# Jetson_Nano_Power_-2.net
KiCad netlist of a schematic drawn in Altium Designer
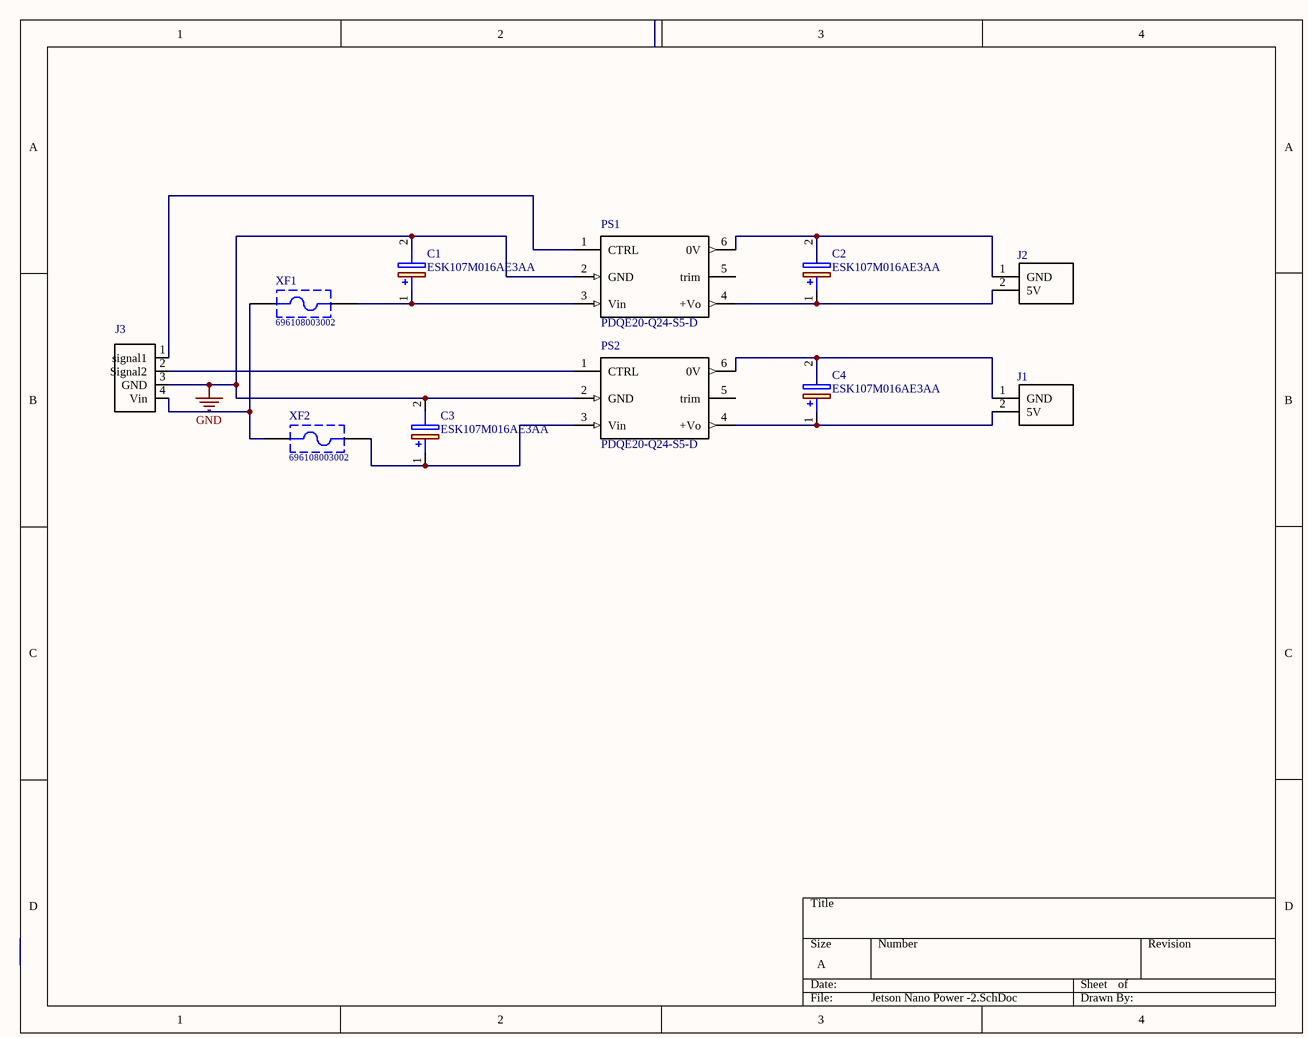
[diagram p0: Jetson Nano Power -2.SchDoc]

(export (version "E")
  (design (tool "Eeschema 10.0.6"))
  (components
    (comp (ref "C1")
      (value "ESK107M016AE3AA")
      (footprint "CAPPRD250W50D630H1250")
      (description "Capacitor Polarised")
      (libsource (lib "80-ESK107M016AE3AA") (part "ESK107M016AE3AA"))
    )
    (comp (ref "C2")
      (value "ESK107M016AE3AA")
      (footprint "CAPPRD250W50D630H1250")
      (description "Capacitor Polarised")
      (libsource (lib "80-ESK107M016AE3AA") (part "ESK107M016AE3AA"))
    )
    (comp (ref "C3")
      (value "ESK107M016AE3AA")
      (footprint "CAPPRD250W50D630H1250")
      (description "Capacitor Polarised")
      (libsource (lib "80-ESK107M016AE3AA") (part "ESK107M016AE3AA"))
    )
    (comp (ref "C4")
      (value "ESK107M016AE3AA")
      (footprint "CAPPRD250W50D630H1250")
      (description "Capacitor Polarised")
      (libsource (lib "80-ESK107M016AE3AA") (part "ESK107M016AE3AA"))
    )
    (comp (ref "J1")
      (value "282856-2")
      (footprint "*TE_282856-2")
      (description "TERMI-BLOK PCB MOUNT 2P")
      (fields (field (name "MF") "TE Connectivity"))
      (libsource (lib "282856-2") (part "282856-2"))
    )
    (comp (ref "J2")
      (value "282856-2")
      (footprint "*TE_282856-2")
      (description "TERMI-BLOK PCB MOUNT 2P")
      (fields (field (name "MF") "TE Connectivity"))
      (libsource (lib "282856-2") (part "282856-2"))
    )
    (comp (ref "J3")
      (value "282836-4")
      (footprint "*TE_282836-4")
      (description "4 Position Wire to Board Terminal Block Horizontal with Board 0.197 _5.00mm_ Through Hole")
      (fields (field (name "MF") "TE Connectivity"))
      (libsource (lib "282836-4") (part "282836-4"))
    )
    (comp (ref "PS1")
      (value "PDQE20-Q24-S5-D")
      (footprint "*CONV_PDQE20-Q24-S5-D")
      (description "20 W, 4:1 Input Range, Single/Dual Regulated Output, DIP, 1500 Vdc Isolation, Dc-Dc Converter")
      (fields (field (name "MF") "CUI Inc.") (field (name "DIGI-KEY_PART_NUMBER") "102-6267-ND"))
      (libsource (lib "PDQE20-Q24-S5-D") (part "PDQE20-Q24-S5-D"))
    )
    (comp (ref "PS2")
      (value "PDQE20-Q24-S5-D")
      (footprint "*CONV_PDQE20-Q24-S5-D")
      (description "20 W, 4:1 Input Range, Single/Dual Regulated Output, DIP, 1500 Vdc Isolation, Dc-Dc Converter")
      (fields (field (name "MF") "CUI Inc.") (field (name "DIGI-KEY_PART_NUMBER") "102-6267-ND"))
      (libsource (lib "PDQE20-Q24-S5-D") (part "PDQE20-Q24-S5-D"))
    )
    (comp (ref "XF1")
      (value "696108003002")
      (footprint "696108003002")
      (description "WR-FSH Fuse Holder Blocks Fuse Holder Blocks Clip Cover for PCB")
      (fields (field (name "MANUFACTURER") "Wurth Elektronik") (field (name "PUBLISHER") "WurthElektronik"))
      (libsource (lib "Altium Content Vault") (part "WE-FUSE-2"))
    )
    (comp (ref "XF2")
      (value "696108003002")
      (footprint "696108003002")
      (description "WR-FSH Fuse Holder Blocks Fuse Holder Blocks Clip Cover for PCB")
      (fields (field (name "MANUFACTURER") "Wurth Elektronik") (field (name "PUBLISHER") "WurthElektronik"))
      (libsource (lib "Altium Content Vault") (part "WE-FUSE-2"))
    )
  )
  (nets
    (net (code "1") (name "GND") (class "Default")
      (node (ref "C1") (pin "2") (pinfunction "-_2") (pintype "passive"))
      (node (ref "C3") (pin "2") (pinfunction "-_2") (pintype "passive"))
      (node (ref "J3") (pin "3") (pinfunction "GND_3") (pintype "passive"))
      (node (ref "PS1") (pin "2") (pinfunction "GND_2") (pintype "input"))
      (node (ref "PS2") (pin "2") (pinfunction "GND_2") (pintype "input"))
    )
    (net (code "2") (name "Net-(C1-+)") (class "Default")
      (node (ref "C1") (pin "1") (pinfunction "+_1") (pintype "passive"))
      (node (ref "PS1") (pin "3") (pinfunction "Vin_3") (pintype "input"))
      (node (ref "XF1") (pin "2") (pinfunction "2_2") (pintype "passive"))
    )
    (net (code "3") (name "Net-(C2-+)") (class "Default")
      (node (ref "C2") (pin "1") (pinfunction "+_1") (pintype "passive"))
      (node (ref "J2") (pin "2") (pinfunction "5V_2") (pintype "passive"))
      (node (ref "PS1") (pin "4") (pinfunction "+Vo_4") (pintype "output"))
    )
    (net (code "4") (name "Net-(C2--)") (class "Default")
      (node (ref "C2") (pin "2") (pinfunction "-_2") (pintype "passive"))
      (node (ref "J2") (pin "1") (pinfunction "GND_1") (pintype "passive"))
      (node (ref "PS1") (pin "6") (pinfunction "0V_6") (pintype "output"))
    )
    (net (code "5") (name "Net-(C3-+)") (class "Default")
      (node (ref "C3") (pin "1") (pinfunction "+_1") (pintype "passive"))
      (node (ref "PS2") (pin "3") (pinfunction "Vin_3") (pintype "input"))
      (node (ref "XF2") (pin "2") (pinfunction "2_2") (pintype "passive"))
    )
    (net (code "6") (name "Net-(C4-+)") (class "Default")
      (node (ref "C4") (pin "1") (pinfunction "+_1") (pintype "passive"))
      (node (ref "J1") (pin "2") (pinfunction "5V_2") (pintype "passive"))
      (node (ref "PS2") (pin "4") (pinfunction "+Vo_4") (pintype "output"))
    )
    (net (code "7") (name "Net-(C4--)") (class "Default")
      (node (ref "C4") (pin "2") (pinfunction "-_2") (pintype "passive"))
      (node (ref "J1") (pin "1") (pinfunction "GND_1") (pintype "passive"))
      (node (ref "PS2") (pin "6") (pinfunction "0V_6") (pintype "output"))
    )
    (net (code "8") (name "Net-(J3-Signal2)") (class "Default")
      (node (ref "J3") (pin "2") (pinfunction "Signal2_2") (pintype "passive"))
      (node (ref "PS2") (pin "1") (pinfunction "CTRL_1") (pintype "open_collector"))
    )
    (net (code "9") (name "Net-(J3-Vin)") (class "Default")
      (node (ref "J3") (pin "4") (pinfunction "Vin_4") (pintype "passive"))
      (node (ref "XF1") (pin "1") (pinfunction "1_1") (pintype "passive"))
      (node (ref "XF2") (pin "1") (pinfunction "1_1") (pintype "passive"))
    )
    (net (code "10") (name "Net-(J3-signal1)") (class "Default")
      (node (ref "J3") (pin "1") (pinfunction "signal1_1") (pintype "passive"))
      (node (ref "PS1") (pin "1") (pinfunction "CTRL_1") (pintype "open_collector"))
    )
    (net (code "11") (name "unconnected-(PS1-trim-Pad5)") (class "Default")
      (node (ref "PS1") (pin "5") (pinfunction "trim_5") (pintype "passive"))
    )
    (net (code "12") (name "unconnected-(PS2-trim-Pad5)") (class "Default")
      (node (ref "PS2") (pin "5") (pinfunction "trim_5") (pintype "passive"))
    )
  )
)
